# HD210_MLL-Range-Extender_v006-X.net
KiCad netlist of a schematic drawn in EAGLE
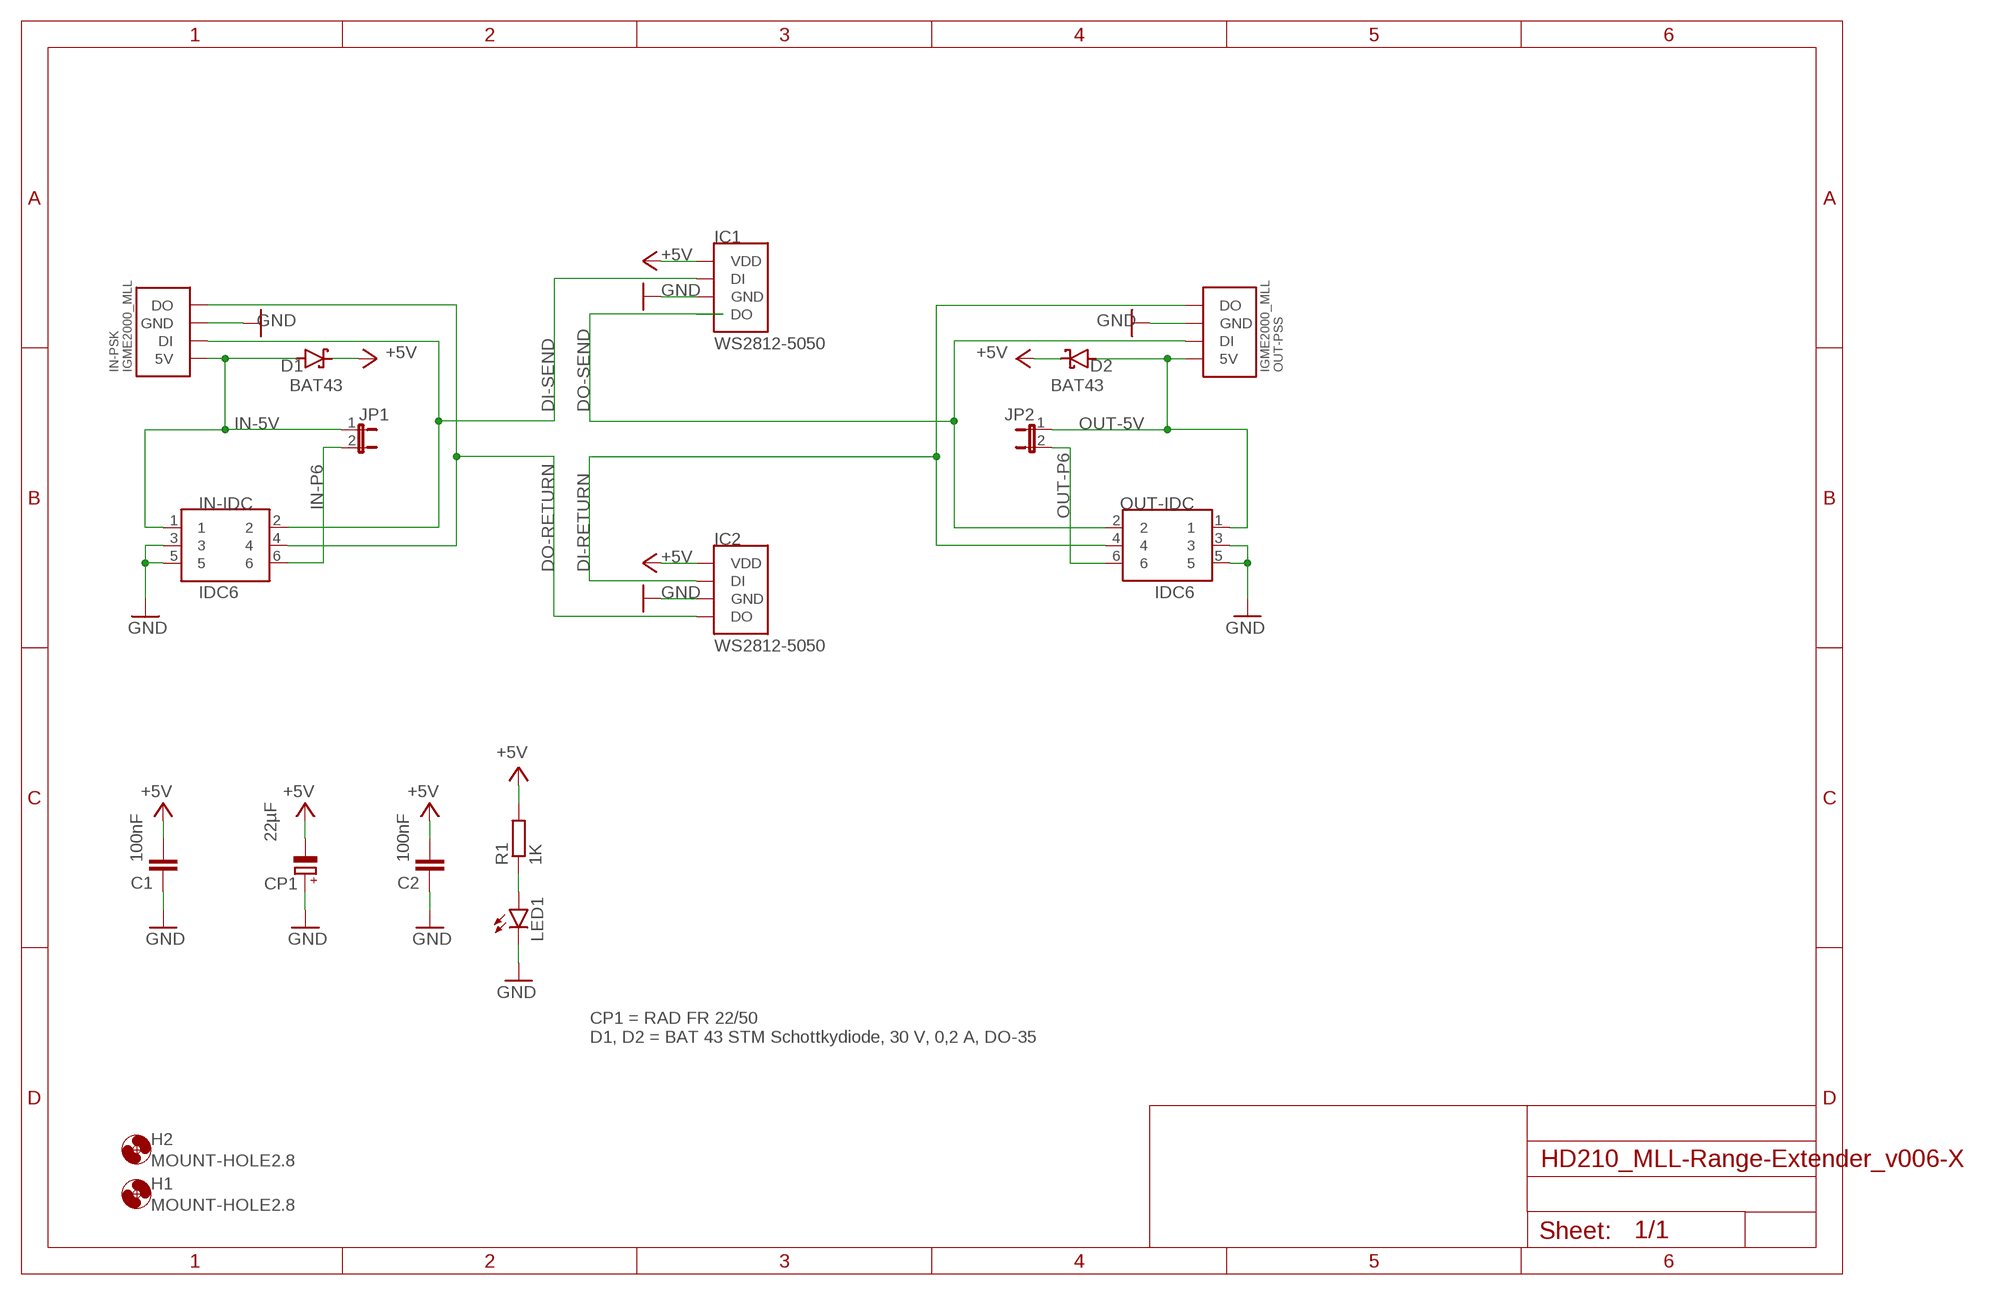
[diagram p0: schematic, sheet 1]

(export (version "E")
  (design (tool "Eeschema 10.0.6"))
  (components
    (comp (ref "C1")
      (value "100nF")
      (footprint "eagle-import:C025-025X050")
      (libsource (lib "eagle-import") (part "C-EU025-025X050"))
    )
    (comp (ref "C2")
      (value "100nF")
      (footprint "eagle-import:C025-025X050")
      (libsource (lib "eagle-import") (part "C-EU025-025X050"))
    )
    (comp (ref "CP1")
      (value "22µF")
      (footprint "eagle-import:E2-5")
      (libsource (lib "eagle-import") (part "CPOL-EUE2-5"))
    )
    (comp (ref "D1")
      (value "BAT43")
      (footprint "eagle-import:DO35-10")
      (libsource (lib "eagle-import") (part "BAT42"))
    )
    (comp (ref "D2")
      (value "BAT43")
      (footprint "eagle-import:DO35-10")
      (libsource (lib "eagle-import") (part "BAT42"))
    )
    (comp (ref "H1")
      (value "MOUNT-HOLE2.8")
      (footprint "eagle-import:2,8")
      (libsource (lib "eagle-import") (part "MOUNT-HOLE2.8"))
    )
    (comp (ref "H2")
      (value "MOUNT-HOLE2.8")
      (footprint "eagle-import:2,8")
      (libsource (lib "eagle-import") (part "MOUNT-HOLE2.8"))
    )
    (comp (ref "IC1")
      (value "WS2812-5050")
      (footprint "eagle-import:5050")
      (libsource (lib "eagle-import") (part "WS2812-5050"))
    )
    (comp (ref "IC2")
      (value "WS2812-5050")
      (footprint "eagle-import:5050")
      (libsource (lib "eagle-import") (part "WS2812-5050"))
    )
    (comp (ref "IN-IDC")
      (value "IDC6")
      (footprint "eagle-import:IDC6")
      (libsource (lib "eagle-import") (part "IDC6"))
    )
    (comp (ref "IN-PSK")
      (value "IGME2000_MLL")
      (footprint "eagle-import:PSSW4-SHORT")
      (libsource (lib "eagle-import") (part "IGME2000_MLL"))
    )
    (comp (ref "JP1")
      (value "JP1E")
      (footprint "eagle-import:JP1")
      (libsource (lib "eagle-import") (part "JP1E"))
    )
    (comp (ref "JP2")
      (value "JP1E")
      (footprint "eagle-import:JP1")
      (libsource (lib "eagle-import") (part "JP1E"))
    )
    (comp (ref "LED1")
      (value "LED3MM")
      (footprint "eagle-import:LED3MM")
      (libsource (lib "eagle-import") (part "LED3MM"))
    )
    (comp (ref "OUT-IDC")
      (value "IDC6")
      (footprint "eagle-import:IDC6")
      (libsource (lib "eagle-import") (part "IDC6"))
    )
    (comp (ref "OUT-PSS")
      (value "IGME2000_MLL")
      (footprint "eagle-import:PSSW4-SHORT")
      (libsource (lib "eagle-import") (part "IGME2000_MLL"))
    )
    (comp (ref "R1")
      (value "1K")
      (footprint "eagle-import:0207_10")
      (libsource (lib "eagle-import") (part "R-EU_0207/10"))
    )
  )
  (nets
    (net (code "1") (name "+5V") (class "Default")
      (node (ref "C1") (pin "2") (pinfunction "2_2") (pintype "passive"))
      (node (ref "C2") (pin "2") (pinfunction "2_2") (pintype "passive"))
      (node (ref "CP1") (pin "-") (pinfunction "-_-") (pintype "passive"))
      (node (ref "D1") (pin "C") (pinfunction "C_C") (pintype "passive"))
      (node (ref "D2") (pin "C") (pinfunction "C_C") (pintype "passive"))
      (node (ref "IC1") (pin "VCC") (pinfunction "VDD_VCC") (pintype "power_in"))
      (node (ref "IC2") (pin "VCC") (pinfunction "VDD_VCC") (pintype "power_in"))
      (node (ref "R1") (pin "2") (pinfunction "2_2") (pintype "passive"))
    )
    (net (code "2") (name "/DI-RETURN") (class "Default")
      (node (ref "IC2") (pin "DI") (pinfunction "DI_DI") (pintype "input"))
      (node (ref "OUT-IDC") (pin "4") (pinfunction "4_4") (pintype "bidirectional"))
      (node (ref "OUT-PSS") (pin "P$1") (pinfunction "DO_P$1") (pintype "output"))
    )
    (net (code "3") (name "/DI-SEND") (class "Default")
      (node (ref "IC1") (pin "DI") (pinfunction "DI_DI") (pintype "input"))
      (node (ref "IN-IDC") (pin "2") (pinfunction "2_2") (pintype "bidirectional"))
      (node (ref "IN-PSK") (pin "P$2") (pinfunction "DI_P$2") (pintype "input"))
    )
    (net (code "4") (name "/DO-RETURN") (class "Default")
      (node (ref "IC2") (pin "DO") (pinfunction "DO_DO") (pintype "output"))
      (node (ref "IN-IDC") (pin "4") (pinfunction "4_4") (pintype "bidirectional"))
      (node (ref "IN-PSK") (pin "P$1") (pinfunction "DO_P$1") (pintype "output"))
    )
    (net (code "5") (name "/DO-SEND") (class "Default")
      (node (ref "IC1") (pin "DO") (pinfunction "DO_DO") (pintype "output"))
      (node (ref "OUT-IDC") (pin "2") (pinfunction "2_2") (pintype "bidirectional"))
      (node (ref "OUT-PSS") (pin "P$2") (pinfunction "DI_P$2") (pintype "input"))
    )
    (net (code "6") (name "/IN-5V") (class "Default")
      (node (ref "D1") (pin "A") (pinfunction "A_A") (pintype "passive"))
      (node (ref "IN-IDC") (pin "1") (pinfunction "1_1") (pintype "bidirectional"))
      (node (ref "IN-PSK") (pin "P$3") (pinfunction "5V_P$3") (pintype "power_in"))
      (node (ref "JP1") (pin "1") (pinfunction "1_1") (pintype "passive"))
    )
    (net (code "7") (name "/IN-P6") (class "Default")
      (node (ref "IN-IDC") (pin "6") (pinfunction "6_6") (pintype "bidirectional"))
      (node (ref "JP1") (pin "2") (pinfunction "2_2") (pintype "passive"))
    )
    (net (code "8") (name "/OUT-5V") (class "Default")
      (node (ref "D2") (pin "A") (pinfunction "A_A") (pintype "passive"))
      (node (ref "JP2") (pin "1") (pinfunction "1_1") (pintype "passive"))
      (node (ref "OUT-IDC") (pin "1") (pinfunction "1_1") (pintype "bidirectional"))
      (node (ref "OUT-PSS") (pin "P$3") (pinfunction "5V_P$3") (pintype "power_in"))
    )
    (net (code "9") (name "/OUT-P6") (class "Default")
      (node (ref "JP2") (pin "2") (pinfunction "2_2") (pintype "passive"))
      (node (ref "OUT-IDC") (pin "6") (pinfunction "6_6") (pintype "bidirectional"))
    )
    (net (code "10") (name "GND") (class "Default")
      (node (ref "C1") (pin "1") (pinfunction "1_1") (pintype "passive"))
      (node (ref "C2") (pin "1") (pinfunction "1_1") (pintype "passive"))
      (node (ref "CP1") (pin "+") (pinfunction "+_+") (pintype "passive"))
      (node (ref "IC1") (pin "GND") (pinfunction "GND_GND") (pintype "power_in"))
      (node (ref "IC2") (pin "GND") (pinfunction "GND_GND") (pintype "power_in"))
      (node (ref "IN-IDC") (pin "3") (pinfunction "3_3") (pintype "bidirectional"))
      (node (ref "IN-IDC") (pin "5") (pinfunction "5_5") (pintype "bidirectional"))
      (node (ref "IN-PSK") (pin "P$4") (pinfunction "GND_P$4") (pintype "power_in"))
      (node (ref "LED1") (pin "K") (pinfunction "C_K") (pintype "passive"))
      (node (ref "OUT-IDC") (pin "3") (pinfunction "3_3") (pintype "bidirectional"))
      (node (ref "OUT-IDC") (pin "5") (pinfunction "5_5") (pintype "bidirectional"))
      (node (ref "OUT-PSS") (pin "P$4") (pinfunction "GND_P$4") (pintype "power_in"))
    )
    (net (code "11") (name "Net-(LED1-PadA)") (class "Default")
      (node (ref "LED1") (pin "A") (pinfunction "A_A") (pintype "passive"))
      (node (ref "R1") (pin "1") (pinfunction "1_1") (pintype "passive"))
    )
  )
)
